# BrewMonitor-v1_0.net
KiCad netlist of a schematic drawn in EAGLE
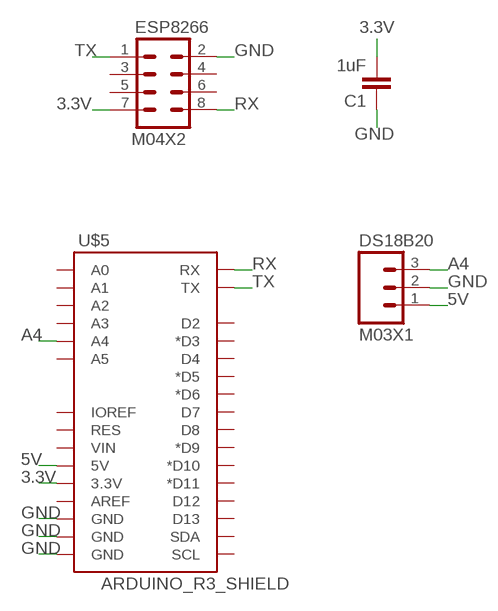
[diagram p0: schematic, sheet 1]

(export (version "E")
  (design (tool "Eeschema 10.0.6"))
  (components
    (comp (ref "C1")
      (value "1uF")
      (footprint "eagle-import:CAP-PTH-SMALL")
      (libsource (lib "eagle-import") (part "CAPPTH"))
    )
    (comp (ref "DS18B20")
      (value "M03X1")
      (footprint "eagle-import:SCREWTERMINAL-3.5MM-3")
      (libsource (lib "eagle-import") (part "M03SCREW"))
    )
    (comp (ref "ESP8266")
      (value "M04X2")
      (footprint "eagle-import:2X4")
      (libsource (lib "eagle-import") (part "M04X2"))
    )
    (comp (ref "U$5")
      (value "ARDUINO_R3_SHIELD")
      (footprint "eagle-import:UNO_R3_SHIELD")
      (libsource (lib "eagle-import") (part "ARDUINO_R3_SHIELD"))
    )
  )
  (nets
    (net (code "1") (name "/3.3V") (class "Default")
      (node (ref "C1") (pin "2") (pinfunction "2_2") (pintype "passive"))
      (node (ref "ESP8266") (pin "7") (pinfunction "7_7") (pintype "passive"))
      (node (ref "U$5") (pin "3.3V") (pinfunction "3.3V_3.3V") (pintype "bidirectional"))
    )
    (net (code "2") (name "/5V") (class "Default")
      (node (ref "DS18B20") (pin "1") (pinfunction "1_1") (pintype "passive"))
      (node (ref "U$5") (pin "5V") (pinfunction "5V_5V") (pintype "bidirectional"))
    )
    (net (code "3") (name "/A4") (class "Default")
      (node (ref "DS18B20") (pin "3") (pinfunction "3_3") (pintype "passive"))
      (node (ref "U$5") (pin "A4") (pinfunction "A4_A4") (pintype "bidirectional"))
    )
    (net (code "4") (name "/GND") (class "Default")
      (node (ref "C1") (pin "1") (pinfunction "1_1") (pintype "passive"))
      (node (ref "DS18B20") (pin "2") (pinfunction "2_2") (pintype "passive"))
      (node (ref "ESP8266") (pin "2") (pinfunction "2_2") (pintype "passive"))
      (node (ref "U$5") (pin "GND@0") (pinfunction "GND_GND@0") (pintype "bidirectional"))
      (node (ref "U$5") (pin "GND@1") (pinfunction "GND_GND@1") (pintype "bidirectional"))
      (node (ref "U$5") (pin "GND@2") (pinfunction "GND_GND@2") (pintype "bidirectional"))
    )
    (net (code "5") (name "/RX") (class "Default")
      (node (ref "ESP8266") (pin "8") (pinfunction "8_8") (pintype "passive"))
      (node (ref "U$5") (pin "RX") (pinfunction "RX_RX") (pintype "bidirectional"))
    )
    (net (code "6") (name "/TX") (class "Default")
      (node (ref "ESP8266") (pin "1") (pinfunction "1_1") (pintype "passive"))
      (node (ref "U$5") (pin "TX") (pinfunction "TX_TX") (pintype "bidirectional"))
    )
    (net (code "7") (name "unconnected-(ESP8266-Pad3)") (class "Default")
      (node (ref "ESP8266") (pin "3") (pinfunction "3_3") (pintype "passive"))
    )
    (net (code "8") (name "unconnected-(ESP8266-Pad4)") (class "Default")
      (node (ref "ESP8266") (pin "4") (pinfunction "4_4") (pintype "passive"))
    )
    (net (code "9") (name "unconnected-(ESP8266-Pad5)") (class "Default")
      (node (ref "ESP8266") (pin "5") (pinfunction "5_5") (pintype "passive"))
    )
    (net (code "10") (name "unconnected-(ESP8266-Pad6)") (class "Default")
      (node (ref "ESP8266") (pin "6") (pinfunction "6_6") (pintype "passive"))
    )
    (net (code "11") (name "unconnected-(U$5-*D3-PadD3)") (class "Default")
      (node (ref "U$5") (pin "D3") (pinfunction "*D3_D3") (pintype "bidirectional"))
    )
    (net (code "12") (name "unconnected-(U$5-*D5-PadD5)") (class "Default")
      (node (ref "U$5") (pin "D5") (pinfunction "*D5_D5") (pintype "bidirectional"))
    )
    (net (code "13") (name "unconnected-(U$5-*D6-PadD6)") (class "Default")
      (node (ref "U$5") (pin "D6") (pinfunction "*D6_D6") (pintype "bidirectional"))
    )
    (net (code "14") (name "unconnected-(U$5-*D9-PadD9)") (class "Default")
      (node (ref "U$5") (pin "D9") (pinfunction "*D9_D9") (pintype "bidirectional"))
    )
    (net (code "15") (name "unconnected-(U$5-*D10-PadD10)") (class "Default")
      (node (ref "U$5") (pin "D10") (pinfunction "*D10_D10") (pintype "bidirectional"))
    )
    (net (code "16") (name "unconnected-(U$5-*D11-PadD11)") (class "Default")
      (node (ref "U$5") (pin "D11") (pinfunction "*D11_D11") (pintype "bidirectional"))
    )
    (net (code "17") (name "unconnected-(U$5-PadA0)") (class "Default")
      (node (ref "U$5") (pin "A0") (pinfunction "A0_A0") (pintype "bidirectional"))
    )
    (net (code "18") (name "unconnected-(U$5-PadA1)") (class "Default")
      (node (ref "U$5") (pin "A1") (pinfunction "A1_A1") (pintype "bidirectional"))
    )
    (net (code "19") (name "unconnected-(U$5-PadA2)") (class "Default")
      (node (ref "U$5") (pin "A2") (pinfunction "A2_A2") (pintype "bidirectional"))
    )
    (net (code "20") (name "unconnected-(U$5-PadA3)") (class "Default")
      (node (ref "U$5") (pin "A3") (pinfunction "A3_A3") (pintype "bidirectional"))
    )
    (net (code "21") (name "unconnected-(U$5-PadA5)") (class "Default")
      (node (ref "U$5") (pin "A5") (pinfunction "A5_A5") (pintype "bidirectional"))
    )
    (net (code "22") (name "unconnected-(U$5-PadAREF)") (class "Default")
      (node (ref "U$5") (pin "AREF") (pinfunction "AREF_AREF") (pintype "bidirectional"))
    )
    (net (code "23") (name "unconnected-(U$5-PadD2)") (class "Default")
      (node (ref "U$5") (pin "D2") (pinfunction "D2_D2") (pintype "bidirectional"))
    )
    (net (code "24") (name "unconnected-(U$5-PadD4)") (class "Default")
      (node (ref "U$5") (pin "D4") (pinfunction "D4_D4") (pintype "bidirectional"))
    )
    (net (code "25") (name "unconnected-(U$5-PadD7)") (class "Default")
      (node (ref "U$5") (pin "D7") (pinfunction "D7_D7") (pintype "bidirectional"))
    )
    (net (code "26") (name "unconnected-(U$5-PadD8)") (class "Default")
      (node (ref "U$5") (pin "D8") (pinfunction "D8_D8") (pintype "bidirectional"))
    )
    (net (code "27") (name "unconnected-(U$5-PadD12)") (class "Default")
      (node (ref "U$5") (pin "D12") (pinfunction "D12_D12") (pintype "bidirectional"))
    )
    (net (code "28") (name "unconnected-(U$5-PadD13)") (class "Default")
      (node (ref "U$5") (pin "D13") (pinfunction "D13_D13") (pintype "bidirectional"))
    )
    (net (code "29") (name "unconnected-(U$5-PadIOREF)") (class "Default")
      (node (ref "U$5") (pin "IOREF") (pinfunction "IOREF_IOREF") (pintype "bidirectional"))
    )
    (net (code "30") (name "unconnected-(U$5-PadRES)") (class "Default")
      (node (ref "U$5") (pin "RES") (pinfunction "RES_RES") (pintype "bidirectional"))
    )
    (net (code "31") (name "unconnected-(U$5-PadSCL)") (class "Default")
      (node (ref "U$5") (pin "SCL") (pinfunction "SCL_SCL") (pintype "bidirectional"))
    )
    (net (code "32") (name "unconnected-(U$5-PadSDA)") (class "Default")
      (node (ref "U$5") (pin "SDA") (pinfunction "SDA_SDA") (pintype "bidirectional"))
    )
    (net (code "33") (name "unconnected-(U$5-PadVIN)") (class "Default")
      (node (ref "U$5") (pin "VIN") (pinfunction "VIN_VIN") (pintype "bidirectional"))
    )
  )
)
